# Powersupply.net
KiCad netlist of a schematic drawn in Altium Designer
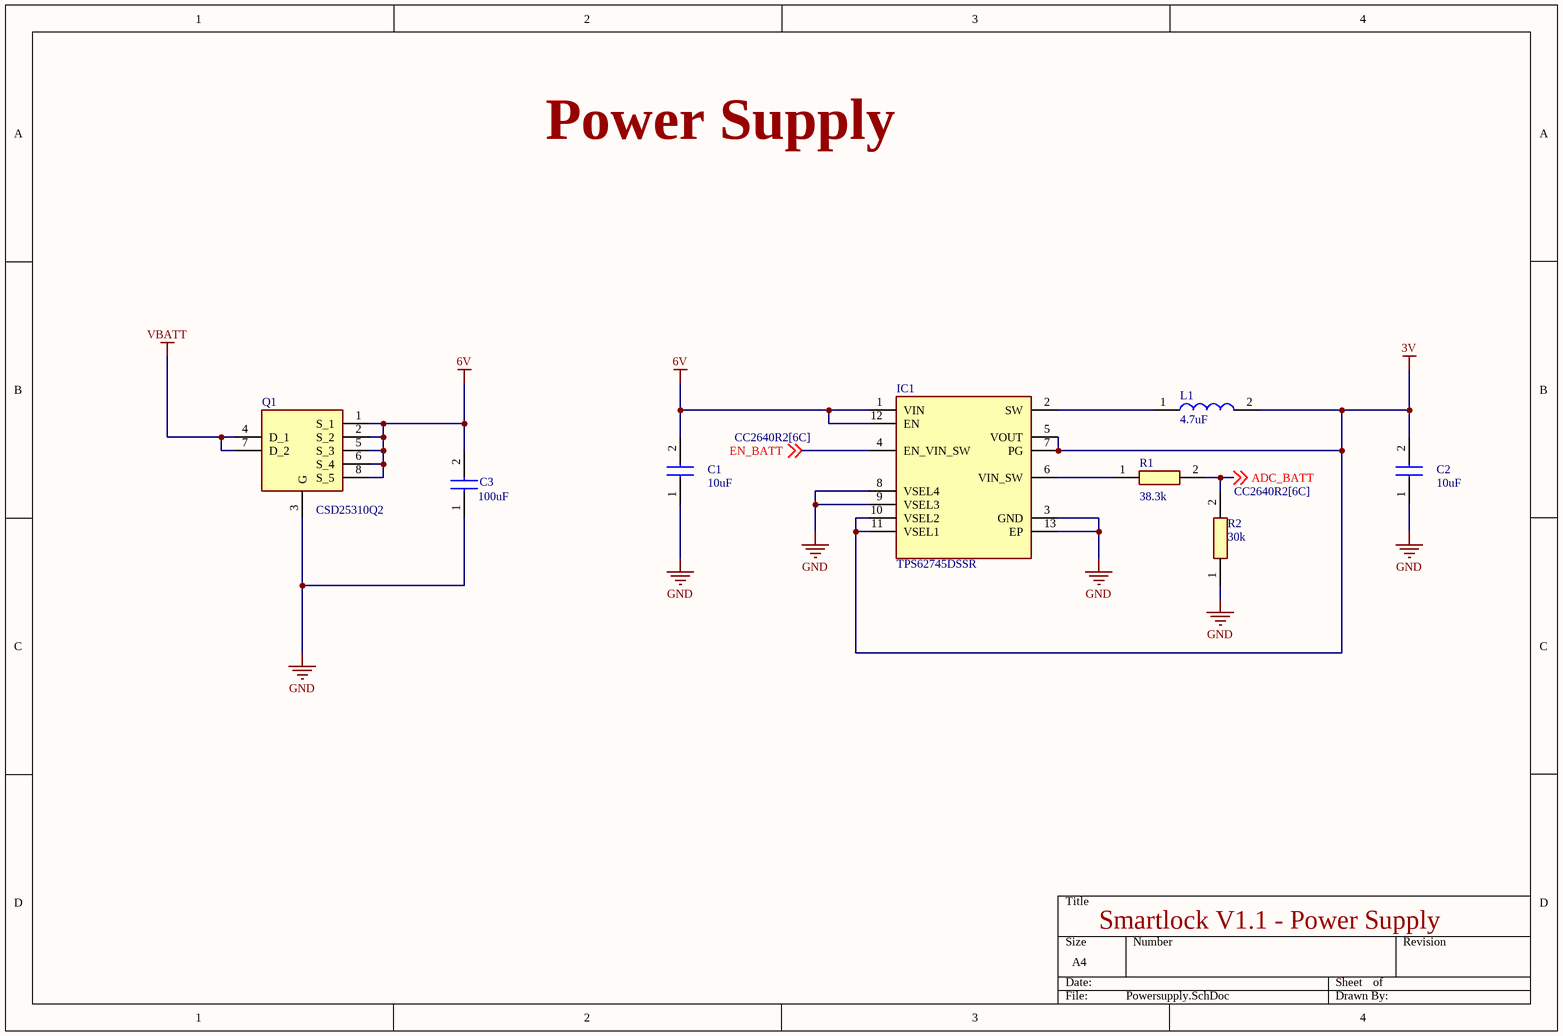
[diagram p0: Powersupply.SchDoc]

(export (version "E")
  (design (tool "Eeschema 10.0.6"))
  (components
    (comp (ref "C1")
      (value "10uF")
      (footprint "Smart_lockV1.1:CAPC2114X145N")
      (description "10uF,16V,X7R")
      (fields
        (field (name "MANUFACTURER_PART_NUMBER") "EMK212BB7106MG-T")
        (field (name "MOUSER PART NUMBER") "963-EMK212BB7106MG-T")
      )
      (libsource (lib "*") (part "EMK212BB7106MG-T"))
    )
    (comp (ref "C2")
      (value "10uF")
      (footprint "Smart_lockV1.1:CAPC2114X145N")
      (description "Capacitor,10uF,16V")
      (fields
        (field (name "MANUFACTURER_PART_NUMBER") "EMK212BB7106MG-T")
        (field (name "MOUSER PART NUMBER") "963-EMK212BB7106MG-T")
      )
      (libsource (lib "*") (part "EMK212BB7106MG-T"))
    )
    (comp (ref "C3")
      (value "100uF")
      (footprint "Smart_lockV1.1:CAPC3216X180N")
      (description "Capacitor,100uF,X7R")
      (fields
        (field (name "MANUFACTURER_PART_NUMBER") "C3216X5R1A107M160AC")
        (field (name "MOUSER PART NUMBER") "810-C3216X5R1A107M")
      )
      (libsource (lib "*") (part "C3216X5R1A107M160AC"))
    )
    (comp (ref "IC1")
      (value "TPS62745DSSR")
      (footprint "Smart_lockV1.1:SON50P200X300X80-13N")
      (description "Integrated Circuit")
      (fields (field (name "MOUSER PART NUMBER") "595-TPS62745DSSR"))
      (libsource (lib "Smart_lockV1.1") (part "TPS62745DSSR"))
    )
    (comp (ref "L1")
      (value "4.7uF")
      (footprint "Smart_lockV1.1:INDC3225X270N")
      (description "Inductor,4.7uF,1.01A,0.1ohm")
      (fields
        (field (name "MANUFACTURER_PART_NUMBER") "CBC3225T4R7MRV")
        (field (name "MOUSER PART NUMBER") "963-CBC3225T4R7MRV")
      )
      (libsource (lib "*") (part "CBC3225T4R7MRV"))
    )
    (comp (ref "Q1")
      (value "CSD25310Q2")
      (footprint "Smart_lockV1.1:CSD17313Q2")
      (description "MOSFET (P-Channel)")
      (fields (field (name "MOUSER PART NUMBER") "595-CSD25310Q2"))
      (libsource (lib "Smart_lockV1.1") (part "CSD25310Q2"))
    )
    (comp (ref "R1")
      (value "38.3k")
      (footprint "Smart_lockV1.1:RESC1608X55N")
      (description "Resistor,38.3k")
      (fields (field (name "MANUFACTURER_PART_NUMBER") "RC0603FR-0738K3L"))
      (libsource (lib "*") (part "RC0603FR-0738K3L"))
    )
    (comp (ref "R2")
      (value "30k")
      (footprint "RESC1608X55N")
      (description "Resistor,30k,1%")
      (fields
        (field (name "MANUFACTURER_PART_NUMBER") "ERJ-3EKF3002V")
        (field (name "MOUSER PART NUMBER") "667-ERJ-3EKF3002V")
      )
      (libsource (lib "Smart_lockV1.1") (part "ERJ-3EKF3002V"))
    )
  )
  (nets
    (net (code "1") (name "3V") (class "Default")
      (node (ref "C2") (pin "2") (pinfunction "2_2") (pintype "passive"))
      (node (ref "IC1") (pin "10") (pinfunction "VSEL2_10") (pintype "passive"))
      (node (ref "IC1") (pin "11") (pinfunction "VSEL1_11") (pintype "passive"))
      (node (ref "IC1") (pin "5") (pinfunction "VOUT_5") (pintype "passive"))
      (node (ref "IC1") (pin "7") (pinfunction "PG_7") (pintype "passive"))
      (node (ref "L1") (pin "2") (pinfunction "2_2") (pintype "passive"))
    )
    (net (code "2") (name "6V") (class "Default")
      (node (ref "C1") (pin "2") (pinfunction "2_2") (pintype "passive"))
      (node (ref "C3") (pin "2") (pinfunction "2_2") (pintype "passive"))
      (node (ref "IC1") (pin "1") (pinfunction "VIN_1") (pintype "passive"))
      (node (ref "IC1") (pin "12") (pinfunction "EN_12") (pintype "passive"))
      (node (ref "Q1") (pin "1") (pinfunction "S_1_1") (pintype "passive"))
      (node (ref "Q1") (pin "2") (pinfunction "S_2_2") (pintype "passive"))
      (node (ref "Q1") (pin "5") (pinfunction "S_3_5") (pintype "passive"))
      (node (ref "Q1") (pin "6") (pinfunction "S_4_6") (pintype "passive"))
      (node (ref "Q1") (pin "8") (pinfunction "S_5_8") (pintype "passive"))
    )
    (net (code "3") (name "ADC_BATT") (class "Default")
      (node (ref "R1") (pin "2") (pinfunction "2_2") (pintype "passive"))
      (node (ref "R2") (pin "2") (pinfunction "2_2") (pintype "passive"))
    )
    (net (code "4") (name "EN_BATT") (class "Default")
      (node (ref "IC1") (pin "4") (pinfunction "EN_VIN_SW_4") (pintype "passive"))
    )
    (net (code "5") (name "GND") (class "Default")
      (node (ref "C1") (pin "1") (pinfunction "1_1") (pintype "passive"))
      (node (ref "C2") (pin "1") (pinfunction "1_1") (pintype "passive"))
      (node (ref "C3") (pin "1") (pinfunction "1_1") (pintype "passive"))
      (node (ref "IC1") (pin "13") (pinfunction "EP_13") (pintype "passive"))
      (node (ref "IC1") (pin "3") (pinfunction "GND_3") (pintype "passive"))
      (node (ref "IC1") (pin "8") (pinfunction "VSEL4_8") (pintype "passive"))
      (node (ref "IC1") (pin "9") (pinfunction "VSEL3_9") (pintype "passive"))
      (node (ref "Q1") (pin "3") (pinfunction "G_3") (pintype "passive"))
      (node (ref "R2") (pin "1") (pinfunction "1_1") (pintype "passive"))
    )
    (net (code "6") (name "Net-(IC1-SW)") (class "Default")
      (node (ref "IC1") (pin "2") (pinfunction "SW_2") (pintype "passive"))
      (node (ref "L1") (pin "1") (pinfunction "1_1") (pintype "passive"))
    )
    (net (code "7") (name "Net-(IC1-VIN_SW)") (class "Default")
      (node (ref "IC1") (pin "6") (pinfunction "VIN_SW_6") (pintype "passive"))
      (node (ref "R1") (pin "1") (pinfunction "1_1") (pintype "passive"))
    )
    (net (code "8") (name "VBATT") (class "Default")
      (node (ref "Q1") (pin "4") (pinfunction "D_1_4") (pintype "passive"))
      (node (ref "Q1") (pin "7") (pinfunction "D_2_7") (pintype "passive"))
    )
  )
)
